# constantCV.net
KiCad netlist of a schematic drawn in Altium Designer
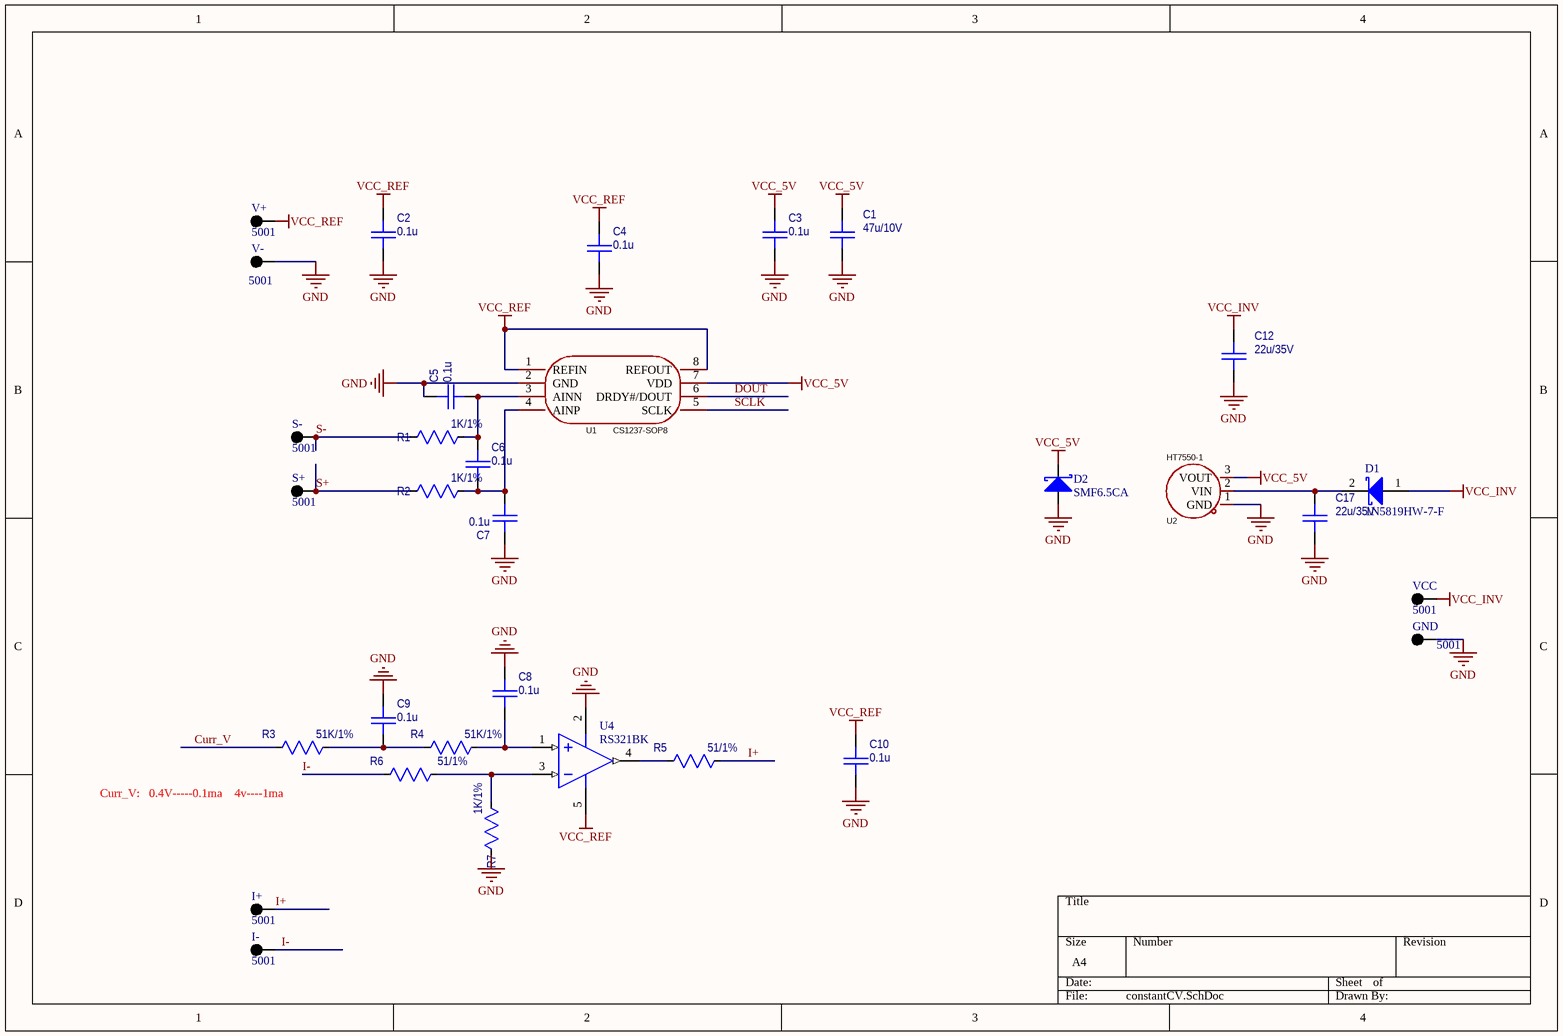
[diagram p0: constantCV.SchDoc]

(export (version "E")
  (design (tool "Eeschema 10.0.6"))
  (components
    (comp (ref "C1")
      (value "47u/10V")
      (footprint "CAPC2012X127N_0805")
      (description "Capacitor, MLCC")
      (fields (field (name "MANUFACTURER") "KEMET") (field (name "PARTNUMBER") "C0805C106K8PACTU"))
      (libsource (lib "Karl") (part "Capacitor_0805"))
    )
    (comp (ref "C2")
      (value "0.1u")
      (footprint "CAPC1608X092N_0603")
      (description "Capacitor, MLCC")
      (fields (field (name "MANUFACTURER") "KEMET") (field (name "PARTNUMBER") "C0603C104M5RACTU"))
      (libsource (lib "Karl") (part "Capacitor_0603"))
    )
    (comp (ref "C3")
      (value "0.1u")
      (footprint "CAPC1608X092N_0603")
      (description "Capacitor, MLCC")
      (fields (field (name "MANUFACTURER") "KEMET") (field (name "PARTNUMBER") "C0603C104M5RACTU"))
      (libsource (lib "Karl") (part "Capacitor_0603"))
    )
    (comp (ref "C4")
      (value "0.1u")
      (footprint "CAPC1608X092N_0603")
      (description "Capacitor, MLCC")
      (fields (field (name "MANUFACTURER") "KEMET") (field (name "PARTNUMBER") "C0603C104M5RACTU"))
      (libsource (lib "Karl") (part "Capacitor_0603"))
    )
    (comp (ref "C5")
      (value "0.1u")
      (footprint "CAPC1608X092N_0603")
      (description "Capacitor, MLCC")
      (fields (field (name "MANUFACTURER") "KEMET") (field (name "PARTNUMBER") "C0603C104M5RACTU"))
      (libsource (lib "Karl") (part "Capacitor_0603"))
    )
    (comp (ref "C6")
      (value "0.1u")
      (footprint "CAPC1608X092N_0603")
      (description "Capacitor, MLCC")
      (fields (field (name "MANUFACTURER") "KEMET") (field (name "PARTNUMBER") "C0603C104M5RACTU"))
      (libsource (lib "Karl") (part "Capacitor_0603"))
    )
    (comp (ref "C7")
      (value "0.1u")
      (footprint "CAPC1608X092N_0603")
      (description "Capacitor, MLCC")
      (fields (field (name "MANUFACTURER") "KEMET") (field (name "PARTNUMBER") "C0603C104M5RACTU"))
      (libsource (lib "Karl") (part "Capacitor_0603"))
    )
    (comp (ref "C8")
      (value "0.1u")
      (footprint "CAPC1608X092N_0603")
      (description "Capacitor, MLCC")
      (fields (field (name "MANUFACTURER") "KEMET") (field (name "PARTNUMBER") "C0603C104M5RACTU"))
      (libsource (lib "Karl") (part "Capacitor_0603"))
    )
    (comp (ref "C9")
      (value "0.1u")
      (footprint "CAPC1608X092N_0603")
      (description "Capacitor, MLCC")
      (fields (field (name "MANUFACTURER") "KEMET") (field (name "PARTNUMBER") "C0603C104M5RACTU"))
      (libsource (lib "Karl") (part "Capacitor_0603"))
    )
    (comp (ref "C10")
      (value "0.1u")
      (footprint "CAPC1608X092N_0603")
      (description "Capacitor, MLCC")
      (fields (field (name "MANUFACTURER") "KEMET") (field (name "PARTNUMBER") "C0603C104M5RACTU"))
      (libsource (lib "Karl") (part "Capacitor_0603"))
    )
    (comp (ref "C12")
      (value "22u/35V")
      (footprint "CAPC2012X127N_0805")
      (description "Capacitor, MLCC")
      (fields (field (name "MANUFACTURER") "KEMET") (field (name "PARTNUMBER") "C0805C106K8PACTU"))
      (libsource (lib "Karl") (part "Capacitor_0805"))
    )
    (comp (ref "C17")
      (value "22u/35V")
      (footprint "CAPC2012X127N_0805")
      (description "Capacitor, MLCC")
      (fields (field (name "MANUFACTURER") "KEMET") (field (name "PARTNUMBER") "C0805C106K8PACTU"))
      (libsource (lib "Karl") (part "Capacitor_0805"))
    )
    (comp (ref "D1")
      (value "1N5819HW-7-F")
      (footprint "DIOD-SOD-123-2_V")
      (libsource (lib "Bogen") (part "1N5819HW-7-F"))
    )
    (comp (ref "D2") (value "SMF6.5CA") (footprint "SOD123") (libsource (lib "*") (part "DIODE S")))
    (comp (ref "GND")
      (value "5001")
      (footprint "KSTN-5001")
      (description "Test Point, Black, 1-Pin THD, RoHS, Bulk")
      (fields (field (name "MANUFACTURER") "Keystone"))
      (libsource (lib "Bogen") (part "5001"))
    )
    (comp (ref "I+")
      (value "5001")
      (footprint "KSTN-5001")
      (description "Test Point, Black, 1-Pin THD, RoHS, Bulk")
      (fields (field (name "MANUFACTURER") "Keystone"))
      (libsource (lib "Bogen") (part "5001"))
    )
    (comp (ref "I-")
      (value "5001")
      (footprint "KSTN-5001")
      (description "Test Point, Black, 1-Pin THD, RoHS, Bulk")
      (fields (field (name "MANUFACTURER") "Keystone"))
      (libsource (lib "Bogen") (part "5001"))
    )
    (comp (ref "R1")
      (value "1K/1%")
      (footprint "RESC1608X055N_0603")
      (description "Resistor, Standard")
      (fields (field (name "MANUFACTURER") "Yageo") (field (name "PARTNUMBER") "RC0603FR-1075KL"))
      (libsource (lib "Karl") (part "Resistor_0603"))
    )
    (comp (ref "R2")
      (value "1K/1%")
      (footprint "RESC1608X055N_0603")
      (description "Resistor, Standard")
      (fields (field (name "MANUFACTURER") "Yageo") (field (name "PARTNUMBER") "RC0603FR-1075KL"))
      (libsource (lib "Karl") (part "Resistor_0603"))
    )
    (comp (ref "R3")
      (value "51K/1%")
      (footprint "RESC1608X055N_0603")
      (description "Resistor, Standard")
      (fields (field (name "MANUFACTURER") "Yageo") (field (name "PARTNUMBER") "RC0603FR-1075KL"))
      (libsource (lib "Karl") (part "Resistor_0603"))
    )
    (comp (ref "R4")
      (value "51K/1%")
      (footprint "RESC1608X055N_0603")
      (description "Resistor, Standard")
      (fields (field (name "MANUFACTURER") "Yageo") (field (name "PARTNUMBER") "RC0603FR-1075KL"))
      (libsource (lib "Karl") (part "Resistor_0603"))
    )
    (comp (ref "R5")
      (value "51/1%")
      (footprint "RESC1608X055N_0603")
      (description "Resistor, Standard")
      (fields (field (name "MANUFACTURER") "Yageo") (field (name "PARTNUMBER") "RC0603FR-1075KL"))
      (libsource (lib "Karl") (part "Resistor_0603"))
    )
    (comp (ref "R6")
      (value "51/1%")
      (footprint "RESC1608X055N_0603")
      (description "Resistor, Standard")
      (fields (field (name "MANUFACTURER") "Yageo") (field (name "PARTNUMBER") "RC0603FR-1075KL"))
      (libsource (lib "Karl") (part "Resistor_0603"))
    )
    (comp (ref "R7")
      (value "1K/1%")
      (footprint "RESC1608X055N_0603")
      (description "Resistor, Standard")
      (fields (field (name "MANUFACTURER") "Yageo") (field (name "PARTNUMBER") "RC0603FR-1075KL"))
      (libsource (lib "Karl") (part "Resistor_0603"))
    )
    (comp (ref "S+")
      (value "5001")
      (footprint "KSTN-5001")
      (description "Test Point, Black, 1-Pin THD, RoHS, Bulk")
      (fields (field (name "MANUFACTURER") "Keystone"))
      (libsource (lib "Bogen") (part "5001"))
    )
    (comp (ref "S-")
      (value "5001")
      (footprint "KSTN-5001")
      (description "Test Point, Black, 1-Pin THD, RoHS, Bulk")
      (fields (field (name "MANUFACTURER") "Keystone"))
      (libsource (lib "Bogen") (part "5001"))
    )
    (comp (ref "U1")
      (value "CS1237-SOP8")
      (footprint "SOIC-8_L5.0-W4.0-P1.27-LS6.0-BL:SOIC-8_L5.0-W4.0-P1.27-LS6.0-BL")
      (fields (field (name "MANUFACTURER") "CHIPSEA(芯海科技)"))
      (libsource (lib "altium-import") (part "root_0_CS1237-SOP8_"))
    )
    (comp (ref "U2")
      (value "HT7550-1")
      (footprint "SOT-89_L4.5-W2.5-P1.50-LS4.2-BR:SOT-89_L4.5-W2.5-P1.50-LS4.2-BR")
      (fields (field (name "MANUFACTURER") "UMW(友台半导体)"))
      (libsource (lib "altium-import") (part "root_2_HT7550-1_C347189_"))
    )
    (comp (ref "U4")
      (value "RS321BK")
      (footprint "SHBL-SOT-23-5_N")
      (fields
        (field (name "MANUFACTURER") "Shanghai Belling")
        (field (name "PARTNUMBER") "BL321LFR")
        (field (name "PUBLISHER") "Bolgen Studio")
      )
      (libsource (lib "Bogen") (part "BL321LFR"))
    )
    (comp (ref "V+")
      (value "5001")
      (footprint "KSTN-5001")
      (description "Test Point, Black, 1-Pin THD, RoHS, Bulk")
      (fields (field (name "MANUFACTURER") "Keystone"))
      (libsource (lib "Bogen") (part "5001"))
    )
    (comp (ref "V-")
      (value "5001")
      (footprint "KSTN-5001")
      (description "Test Point, Black, 1-Pin THD, RoHS, Bulk")
      (fields (field (name "MANUFACTURER") "Keystone"))
      (libsource (lib "Bogen") (part "5001"))
    )
    (comp (ref "VCC")
      (value "5001")
      (footprint "KSTN-5001")
      (description "Test Point, Black, 1-Pin THD, RoHS, Bulk")
      (fields (field (name "MANUFACTURER") "Keystone"))
      (libsource (lib "Bogen") (part "5001"))
    )
  )
  (nets
    (net (code "1") (name "/Curr_V") (class "Default")
      (node (ref "R3") (pin "2") (pinfunction "2_2") (pintype "passive"))
    )
    (net (code "2") (name "/DOUT") (class "Default")
      (node (ref "U1") (pin "6") (pinfunction "DRDY#/DOUT_6") (pintype "passive"))
    )
    (net (code "3") (name "/I+") (class "Default")
      (node (ref "I+") (pin "1") (pintype "passive"))
      (node (ref "R5") (pin "1") (pinfunction "1_1") (pintype "passive"))
    )
    (net (code "4") (name "/I-") (class "Default")
      (node (ref "I-") (pin "1") (pintype "passive"))
      (node (ref "R6") (pin "2") (pinfunction "2_2") (pintype "passive"))
    )
    (net (code "5") (name "/S+") (class "Default")
      (node (ref "R2") (pin "2") (pinfunction "2_2") (pintype "passive"))
      (node (ref "S+") (pin "1") (pintype "passive"))
    )
    (net (code "6") (name "/S-") (class "Default")
      (node (ref "R1") (pin "2") (pinfunction "2_2") (pintype "passive"))
      (node (ref "S-") (pin "1") (pintype "passive"))
    )
    (net (code "7") (name "/SCLK") (class "Default")
      (node (ref "U1") (pin "5") (pinfunction "SCLK_5") (pintype "passive"))
    )
    (net (code "8") (name "GND") (class "Default")
      (node (ref "C1") (pin "2") (pinfunction "2_2") (pintype "passive"))
      (node (ref "C10") (pin "2") (pinfunction "2_2") (pintype "passive"))
      (node (ref "C12") (pin "2") (pinfunction "2_2") (pintype "passive"))
      (node (ref "C17") (pin "2") (pinfunction "2_2") (pintype "passive"))
      (node (ref "C2") (pin "2") (pinfunction "2_2") (pintype "passive"))
      (node (ref "C3") (pin "2") (pinfunction "2_2") (pintype "passive"))
      (node (ref "C4") (pin "2") (pinfunction "2_2") (pintype "passive"))
      (node (ref "C5") (pin "1") (pinfunction "1_1") (pintype "passive"))
      (node (ref "C7") (pin "1") (pinfunction "1_1") (pintype "passive"))
      (node (ref "C8") (pin "1") (pinfunction "1_1") (pintype "passive"))
      (node (ref "C9") (pin "1") (pinfunction "1_1") (pintype "passive"))
      (node (ref "D2") (pin "1") (pinfunction "A_1") (pintype "passive"))
      (node (ref "GND") (pin "1") (pintype "passive"))
      (node (ref "R7") (pin "2") (pinfunction "2_2") (pintype "passive"))
      (node (ref "U1") (pin "2") (pinfunction "GND_2") (pintype "passive"))
      (node (ref "U2") (pin "1") (pinfunction "GND_1") (pintype "passive"))
      (node (ref "U4") (pin "2") (pinfunction "VSS_2") (pintype "power_in"))
      (node (ref "V-") (pin "1") (pintype "passive"))
    )
    (net (code "9") (name "Net-(C9-Pad2)") (class "Default")
      (node (ref "C9") (pin "2") (pinfunction "2_2") (pintype "passive"))
      (node (ref "R3") (pin "1") (pinfunction "1_1") (pintype "passive"))
      (node (ref "R4") (pin "2") (pinfunction "2_2") (pintype "passive"))
    )
    (net (code "10") (name "Net-(D1-K)") (class "Default")
      (node (ref "C17") (pin "1") (pinfunction "1_1") (pintype "passive"))
      (node (ref "D1") (pin "2") (pinfunction "K_2") (pintype "passive"))
      (node (ref "U2") (pin "2") (pinfunction "VIN_2") (pintype "passive"))
    )
    (net (code "11") (name "Net-(U1-AINN)") (class "Default")
      (node (ref "C5") (pin "2") (pinfunction "2_2") (pintype "passive"))
      (node (ref "C6") (pin "1") (pinfunction "1_1") (pintype "passive"))
      (node (ref "R1") (pin "1") (pinfunction "1_1") (pintype "passive"))
      (node (ref "U1") (pin "3") (pinfunction "AINN_3") (pintype "passive"))
    )
    (net (code "12") (name "Net-(U1-AINP)") (class "Default")
      (node (ref "C6") (pin "2") (pinfunction "2_2") (pintype "passive"))
      (node (ref "C7") (pin "2") (pinfunction "2_2") (pintype "passive"))
      (node (ref "R2") (pin "1") (pinfunction "1_1") (pintype "passive"))
      (node (ref "U1") (pin "4") (pinfunction "AINP_4") (pintype "passive"))
    )
    (net (code "13") (name "Net-(U4-IN+)") (class "Default")
      (node (ref "C8") (pin "2") (pinfunction "2_2") (pintype "passive"))
      (node (ref "R4") (pin "1") (pinfunction "1_1") (pintype "passive"))
      (node (ref "U4") (pin "1") (pinfunction "IN+_1") (pintype "input"))
    )
    (net (code "14") (name "Net-(U4-IN-)") (class "Default")
      (node (ref "R6") (pin "1") (pinfunction "1_1") (pintype "passive"))
      (node (ref "R7") (pin "1") (pinfunction "1_1") (pintype "passive"))
      (node (ref "U4") (pin "3") (pinfunction "IN-_3") (pintype "input"))
    )
    (net (code "15") (name "Net-(U4-OUT)") (class "Default")
      (node (ref "R5") (pin "2") (pinfunction "2_2") (pintype "passive"))
      (node (ref "U4") (pin "4") (pinfunction "OUT_4") (pintype "output"))
    )
    (net (code "16") (name "VCC_5V") (class "Default")
      (node (ref "C1") (pin "1") (pinfunction "1_1") (pintype "passive"))
      (node (ref "C3") (pin "1") (pinfunction "1_1") (pintype "passive"))
      (node (ref "D2") (pin "2") (pinfunction "K_2") (pintype "passive"))
      (node (ref "U1") (pin "7") (pinfunction "VDD_7") (pintype "passive"))
      (node (ref "U2") (pin "3") (pinfunction "VOUT_3") (pintype "passive"))
    )
    (net (code "17") (name "VCC_INV") (class "Default")
      (node (ref "C12") (pin "1") (pinfunction "1_1") (pintype "passive"))
      (node (ref "D1") (pin "1") (pinfunction "A_1") (pintype "passive"))
      (node (ref "VCC") (pin "1") (pintype "passive"))
    )
    (net (code "18") (name "VCC_REF") (class "Default")
      (node (ref "C10") (pin "1") (pinfunction "1_1") (pintype "passive"))
      (node (ref "C2") (pin "1") (pinfunction "1_1") (pintype "passive"))
      (node (ref "C4") (pin "1") (pinfunction "1_1") (pintype "passive"))
      (node (ref "U1") (pin "1") (pinfunction "REFIN_1") (pintype "passive"))
      (node (ref "U1") (pin "8") (pinfunction "REFOUT_8") (pintype "passive"))
      (node (ref "U4") (pin "5") (pinfunction "VDD_5") (pintype "power_in"))
      (node (ref "V+") (pin "1") (pintype "passive"))
    )
  )
)
